# plugV13.net
KiCad netlist of a schematic drawn in EAGLE
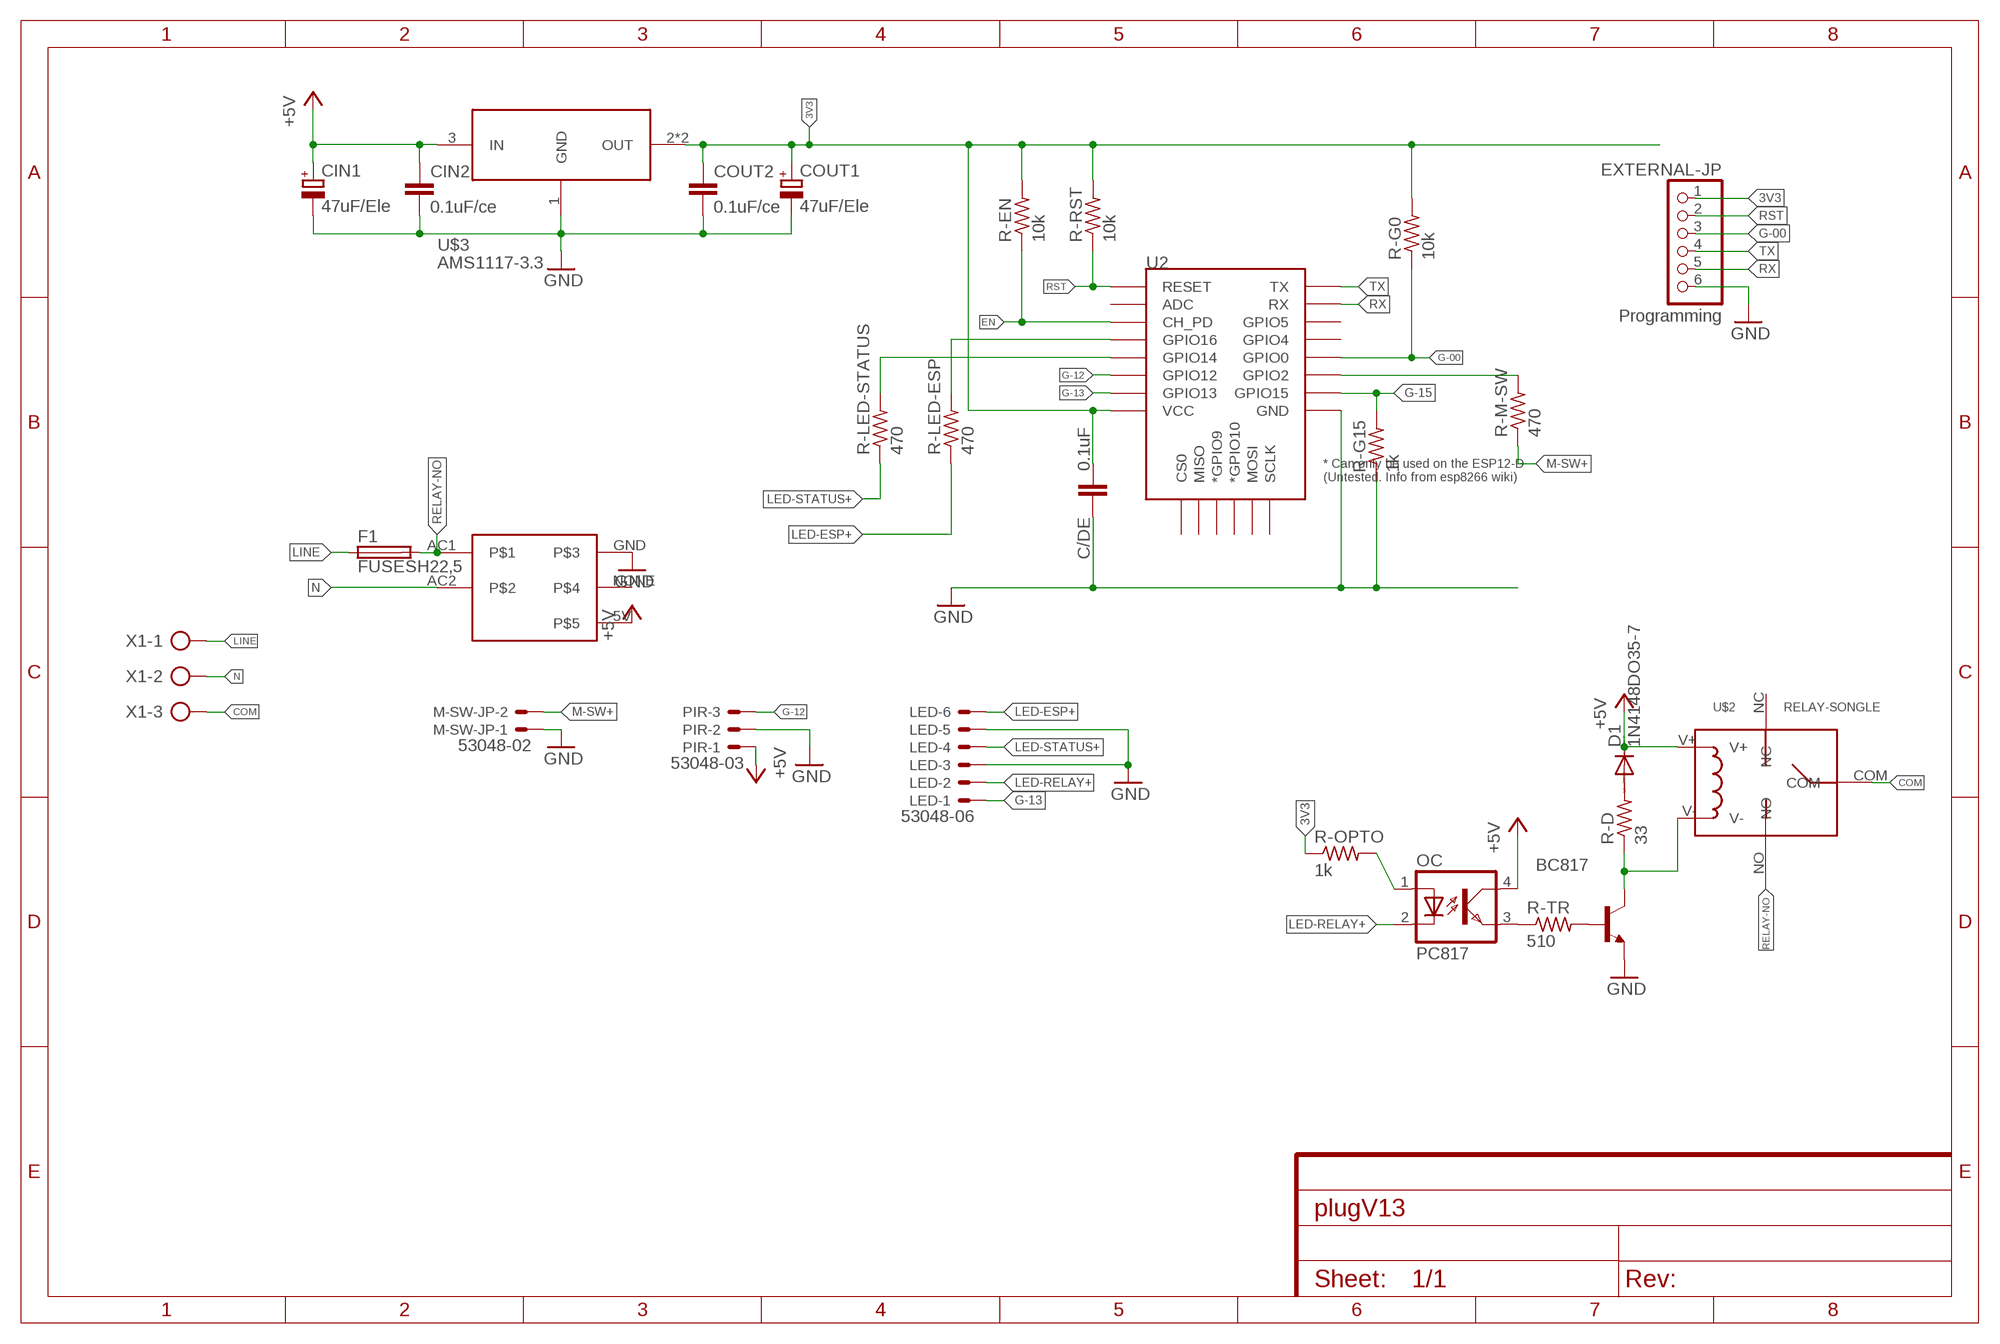
[diagram p0: schematic, sheet 1]

(export (version "E")
  (design (tool "Eeschema 10.0.6"))
  (components
    (comp (ref "BC817")
      (value "BC817-NPN-SOT23-BEC")
      (footprint "eagle-import:SOT23-BEC")
      (libsource (lib "eagle-import") (part "-NPN-SOT23-BECBC817"))
    )
    (comp (ref "C/DE")
      (value "0.1uF")
      (footprint "eagle-import:C0805")
      (libsource (lib "eagle-import") (part "C-EUC0805"))
    )
    (comp (ref "CIN1")
      (value "47uF/Ele")
      (footprint "eagle-import:E2-5")
      (libsource (lib "eagle-import") (part "CPOL-EUE2-5"))
    )
    (comp (ref "CIN2")
      (value "0.1uF/ce")
      (footprint "eagle-import:C0603K")
      (libsource (lib "eagle-import") (part "C-EUC0603K"))
    )
    (comp (ref "COUT1")
      (value "47uF/Ele")
      (footprint "eagle-import:E2-5")
      (libsource (lib "eagle-import") (part "CPOL-EUE2-5"))
    )
    (comp (ref "COUT2")
      (value "0.1uF/ce")
      (footprint "eagle-import:C0603K")
      (libsource (lib "eagle-import") (part "C-EUC0603K"))
    )
    (comp (ref "D1")
      (value "1N4148DO35-7")
      (footprint "eagle-import:DO35-7")
      (libsource (lib "eagle-import") (part "1N4148DO35-7"))
    )
    (comp (ref "EXTERNAL-JP")
      (value "Programming")
      (footprint "eagle-import:1X06")
      (libsource (lib "eagle-import") (part "PINHD-1X6"))
    )
    (comp (ref "F1")
      (value "FUSESH22,5")
      (footprint "eagle-import:SH22,5")
      (libsource (lib "eagle-import") (part "FUSESH22,5"))
    )
    (comp (ref "LED")
      (value "53048-06")
      (footprint "eagle-import:53048-06")
      (fields (field (name "MF") "WALDOM/MOLEX") (field (name "MPN") "53048-0610"))
      (libsource (lib "eagle-import") (part "53?-06048"))
    )
    (comp (ref "M-SW-JP")
      (value "53048-02")
      (footprint "eagle-import:53048-02")
      (fields (field (name "MF") "MOLEX") (field (name "MPN") "53048-0210"))
      (libsource (lib "eagle-import") (part "53?-02048"))
    )
    (comp (ref "OC")
      (value "PC817")
      (footprint "eagle-import:DIL04")
      (fields (field (name "MPN") "PC817X4J000F"))
      (libsource (lib "eagle-import") (part "PC817"))
    )
    (comp (ref "PIR")
      (value "53048-03")
      (footprint "eagle-import:53048-03")
      (fields (field (name "MF") "WALDOM/MOLEX") (field (name "MPN") "53048-0310"))
      (libsource (lib "eagle-import") (part "53?-03048"))
    )
    (comp (ref "R-D")
      (value "33")
      (footprint "eagle-import:M0805")
      (libsource (lib "eagle-import") (part "R-US_M0805"))
    )
    (comp (ref "R-EN")
      (value "10k")
      (footprint "eagle-import:R0603")
      (libsource (lib "eagle-import") (part "R-US_R0603"))
    )
    (comp (ref "R-G0")
      (value "10k")
      (footprint "eagle-import:R0603")
      (libsource (lib "eagle-import") (part "R-US_R0603"))
    )
    (comp (ref "R-G15")
      (value "1k")
      (footprint "eagle-import:R0603")
      (libsource (lib "eagle-import") (part "R-US_R0603"))
    )
    (comp (ref "R-LED-ESP")
      (value "470")
      (footprint "eagle-import:R0603")
      (libsource (lib "eagle-import") (part "R-US_R0603"))
    )
    (comp (ref "R-LED-STATUS")
      (value "470")
      (footprint "eagle-import:R0603")
      (libsource (lib "eagle-import") (part "R-US_R0603"))
    )
    (comp (ref "R-M-SW")
      (value "470")
      (footprint "eagle-import:R0603")
      (libsource (lib "eagle-import") (part "R-US_R0603"))
    )
    (comp (ref "R-OPTO")
      (value "1k")
      (footprint "eagle-import:M0805")
      (libsource (lib "eagle-import") (part "R-US_M0805"))
    )
    (comp (ref "R-RST")
      (value "10k")
      (footprint "eagle-import:R0603")
      (libsource (lib "eagle-import") (part "R-US_R0603"))
    )
    (comp (ref "R-TR")
      (value "510")
      (footprint "eagle-import:M0805")
      (libsource (lib "eagle-import") (part "R-US_M0805"))
    )
    (comp (ref "U$2")
      (value "RELAY-SONGLE")
      (footprint "eagle-import:RELAY-SONGLE")
      (libsource (lib "eagle-import") (part "RELAY-SONGLE"))
    )
    (comp (ref "U$3")
      (value "AMS1117-3.3")
      (footprint "eagle-import:SOT-223")
      (libsource (lib "eagle-import") (part "AMS1117-3.3"))
    )
    (comp (ref "U$4")
      (value "POWERSUPPLY-5V-700MA")
      (footprint "eagle-import:POWERSUPPLY-5V-700MA")
      (libsource (lib "eagle-import") (part "POWERSUPPLY-5V-700MA"))
    )
    (comp (ref "U2")
      (value "ESP12ESMD")
      (footprint "eagle-import:ESP12E-SMD")
      (libsource (lib "eagle-import") (part "ESP12ESMD"))
    )
    (comp (ref "X1")
      (value "AK300/3")
      (footprint "eagle-import:AK300_3")
      (libsource (lib "eagle-import") (part "AK300/3"))
    )
  )
  (nets
    (net (code "1") (name "+5V") (class "Default")
      (node (ref "CIN1") (pin "+") (pinfunction "+_+") (pintype "passive"))
      (node (ref "CIN2") (pin "1") (pinfunction "1_1") (pintype "passive"))
      (node (ref "D1") (pin "C") (pinfunction "C_C") (pintype "passive"))
      (node (ref "OC") (pin "4") (pinfunction "COL_4") (pintype "passive"))
      (node (ref "PIR") (pin "1") (pinfunction "S_1") (pintype "passive"))
      (node (ref "U$2") (pin "V+") (pinfunction "V+_V+") (pintype "bidirectional"))
      (node (ref "U$3") (pin "3") (pinfunction "IN_3") (pintype "input"))
      (node (ref "U$4") (pin "5V") (pinfunction "P$5_5V") (pintype "bidirectional"))
    )
    (net (code "2") (name "3V3") (class "Default")
      (node (ref "C/DE") (pin "1") (pinfunction "1_1") (pintype "passive"))
      (node (ref "COUT1") (pin "+") (pinfunction "+_+") (pintype "passive"))
      (node (ref "COUT2") (pin "1") (pinfunction "1_1") (pintype "passive"))
      (node (ref "EXTERNAL-JP") (pin "1") (pinfunction "1_1") (pintype "passive"))
      (node (ref "R-EN") (pin "2") (pinfunction "2_2") (pintype "passive"))
      (node (ref "R-G0") (pin "2") (pinfunction "2_2") (pintype "passive"))
      (node (ref "R-OPTO") (pin "1") (pinfunction "1_1") (pintype "passive"))
      (node (ref "R-RST") (pin "2") (pinfunction "2_2") (pintype "passive"))
      (node (ref "U$3") (pin "2") (pinfunction "OUT_2") (pintype "output"))
      (node (ref "U$3") (pin "4") (pinfunction "OUT_4") (pintype "output"))
      (node (ref "U2") (pin "VCC") (pinfunction "VCC_VCC") (pintype "bidirectional"))
    )
    (net (code "3") (name "COM") (class "Default")
      (node (ref "U$2") (pin "COM") (pinfunction "COM_COM") (pintype "bidirectional"))
      (node (ref "X1") (pin "3") (pinfunction "KL_3") (pintype "passive"))
    )
    (net (code "4") (name "EN") (class "Default")
      (node (ref "R-EN") (pin "1") (pinfunction "1_1") (pintype "passive"))
      (node (ref "U2") (pin "CH_PD") (pinfunction "CH_PD_CH_PD") (pintype "bidirectional"))
    )
    (net (code "5") (name "G-00") (class "Default")
      (node (ref "EXTERNAL-JP") (pin "3") (pinfunction "3_3") (pintype "passive"))
      (node (ref "R-G0") (pin "1") (pinfunction "1_1") (pintype "passive"))
      (node (ref "U2") (pin "GPIO0") (pinfunction "GPIO0_GPIO0") (pintype "bidirectional"))
    )
    (net (code "6") (name "G-12") (class "Default")
      (node (ref "PIR") (pin "3") (pinfunction "S_3") (pintype "passive"))
      (node (ref "U2") (pin "GPIO12") (pinfunction "GPIO12_GPIO12") (pintype "bidirectional"))
    )
    (net (code "7") (name "G-13") (class "Default")
      (node (ref "LED") (pin "1") (pinfunction "S_1") (pintype "passive"))
      (node (ref "U2") (pin "GPIO13") (pinfunction "GPIO13_GPIO13") (pintype "bidirectional"))
    )
    (net (code "8") (name "G-15") (class "Default")
      (node (ref "R-G15") (pin "2") (pinfunction "2_2") (pintype "passive"))
      (node (ref "U2") (pin "GPIO15") (pinfunction "GPIO15_GPIO15") (pintype "bidirectional"))
    )
    (net (code "9") (name "GND") (class "Default")
      (node (ref "BC817") (pin "E") (pinfunction "E_E") (pintype "passive"))
      (node (ref "C/DE") (pin "2") (pinfunction "2_2") (pintype "passive"))
      (node (ref "CIN1") (pin "-") (pinfunction "-_-") (pintype "passive"))
      (node (ref "CIN2") (pin "2") (pinfunction "2_2") (pintype "passive"))
      (node (ref "COUT1") (pin "-") (pinfunction "-_-") (pintype "passive"))
      (node (ref "COUT2") (pin "2") (pinfunction "2_2") (pintype "passive"))
      (node (ref "EXTERNAL-JP") (pin "6") (pinfunction "6_6") (pintype "passive"))
      (node (ref "LED") (pin "3") (pinfunction "S_3") (pintype "passive"))
      (node (ref "LED") (pin "5") (pinfunction "S_5") (pintype "passive"))
      (node (ref "M-SW-JP") (pin "1") (pinfunction "S_1") (pintype "passive"))
      (node (ref "PIR") (pin "2") (pinfunction "S_2") (pintype "passive"))
      (node (ref "R-G15") (pin "1") (pinfunction "1_1") (pintype "passive"))
      (node (ref "U$3") (pin "1") (pinfunction "GND_1") (pintype "passive"))
      (node (ref "U$4") (pin "GND") (pinfunction "P$3_GND") (pintype "bidirectional"))
      (node (ref "U2") (pin "GND") (pinfunction "GND_GND") (pintype "bidirectional"))
    )
    (net (code "10") (name "LED-ESP+") (class "Default")
      (node (ref "LED") (pin "6") (pinfunction "S_6") (pintype "passive"))
      (node (ref "R-LED-ESP") (pin "1") (pinfunction "1_1") (pintype "passive"))
    )
    (net (code "11") (name "LED-RELAY+") (class "Default")
      (node (ref "LED") (pin "2") (pinfunction "S_2") (pintype "passive"))
      (node (ref "OC") (pin "2") (pinfunction "C_2") (pintype "passive"))
    )
    (net (code "12") (name "LED-STATUS+") (class "Default")
      (node (ref "LED") (pin "4") (pinfunction "S_4") (pintype "passive"))
      (node (ref "R-LED-STATUS") (pin "1") (pinfunction "1_1") (pintype "passive"))
    )
    (net (code "13") (name "LINE") (class "Default")
      (node (ref "F1") (pin "1") (pinfunction "1_1") (pintype "passive"))
      (node (ref "X1") (pin "1") (pinfunction "KL_1") (pintype "passive"))
    )
    (net (code "14") (name "M-SW+") (class "Default")
      (node (ref "M-SW-JP") (pin "2") (pinfunction "S_2") (pintype "passive"))
      (node (ref "R-M-SW") (pin "1") (pinfunction "1_1") (pintype "passive"))
    )
    (net (code "15") (name "N") (class "Default")
      (node (ref "U$4") (pin "AC2") (pinfunction "P$2_AC2") (pintype "bidirectional"))
      (node (ref "X1") (pin "2") (pinfunction "KL_2") (pintype "passive"))
    )
    (net (code "16") (name "Net-(BC817-PadB)") (class "Default")
      (node (ref "BC817") (pin "B") (pinfunction "B_B") (pintype "passive"))
      (node (ref "R-TR") (pin "2") (pinfunction "2_2") (pintype "passive"))
    )
    (net (code "17") (name "Net-(BC817-PadC)") (class "Default")
      (node (ref "BC817") (pin "C") (pinfunction "C_C") (pintype "passive"))
      (node (ref "R-D") (pin "1") (pinfunction "1_1") (pintype "passive"))
      (node (ref "U$2") (pin "V-") (pinfunction "V-_V-") (pintype "bidirectional"))
    )
    (net (code "18") (name "Net-(D1-PadA)") (class "Default")
      (node (ref "D1") (pin "A") (pinfunction "A_A") (pintype "passive"))
      (node (ref "R-D") (pin "2") (pinfunction "2_2") (pintype "passive"))
    )
    (net (code "19") (name "Net-(OC-A)") (class "Default")
      (node (ref "OC") (pin "1") (pinfunction "A_1") (pintype "passive"))
      (node (ref "R-OPTO") (pin "2") (pinfunction "2_2") (pintype "passive"))
    )
    (net (code "20") (name "Net-(OC-EMIT)") (class "Default")
      (node (ref "OC") (pin "3") (pinfunction "EMIT_3") (pintype "passive"))
      (node (ref "R-TR") (pin "1") (pinfunction "1_1") (pintype "passive"))
    )
    (net (code "21") (name "Net-(R-LED-ESP-Pad2)") (class "Default")
      (node (ref "R-LED-ESP") (pin "2") (pinfunction "2_2") (pintype "passive"))
      (node (ref "U2") (pin "GPIO16") (pinfunction "GPIO16_GPIO16") (pintype "bidirectional"))
    )
    (net (code "22") (name "Net-(R-LED-STATUS-Pad2)") (class "Default")
      (node (ref "R-LED-STATUS") (pin "2") (pinfunction "2_2") (pintype "passive"))
      (node (ref "U2") (pin "GPIO14") (pinfunction "GPIO14_GPIO14") (pintype "bidirectional"))
    )
    (net (code "23") (name "Net-(R-M-SW-Pad2)") (class "Default")
      (node (ref "R-M-SW") (pin "2") (pinfunction "2_2") (pintype "passive"))
      (node (ref "U2") (pin "GPIO2") (pinfunction "GPIO2_GPIO2") (pintype "bidirectional"))
    )
    (net (code "24") (name "RELAY-NO") (class "Default")
      (node (ref "F1") (pin "2") (pinfunction "2_2") (pintype "passive"))
      (node (ref "U$2") (pin "NO") (pinfunction "NO_NO") (pintype "bidirectional"))
      (node (ref "U$4") (pin "AC1") (pinfunction "P$1_AC1") (pintype "bidirectional"))
    )
    (net (code "25") (name "RST") (class "Default")
      (node (ref "EXTERNAL-JP") (pin "2") (pinfunction "2_2") (pintype "passive"))
      (node (ref "R-RST") (pin "1") (pinfunction "1_1") (pintype "passive"))
      (node (ref "U2") (pin "RESET") (pinfunction "RESET_RESET") (pintype "bidirectional"))
    )
    (net (code "26") (name "RX") (class "Default")
      (node (ref "EXTERNAL-JP") (pin "5") (pinfunction "5_5") (pintype "passive"))
      (node (ref "U2") (pin "RXD0") (pinfunction "RX_RXD0") (pintype "bidirectional"))
    )
    (net (code "27") (name "TX") (class "Default")
      (node (ref "EXTERNAL-JP") (pin "4") (pinfunction "4_4") (pintype "passive"))
      (node (ref "U2") (pin "TXD0") (pinfunction "TX_TXD0") (pintype "bidirectional"))
    )
    (net (code "28") (name "unconnected-(U$2-PadNC)") (class "Default")
      (node (ref "U$2") (pin "NC") (pinfunction "NC_NC") (pintype "bidirectional"))
    )
    (net (code "29") (name "unconnected-(U$4-P$4-PadNONE)") (class "Default")
      (node (ref "U$4") (pin "NONE") (pinfunction "P$4_NONE") (pintype "bidirectional"))
    )
    (net (code "30") (name "unconnected-(U2-*GPIO9-PadGPIO9)") (class "Default")
      (node (ref "U2") (pin "GPIO9") (pinfunction "*GPIO9_GPIO9") (pintype "bidirectional"))
    )
    (net (code "31") (name "unconnected-(U2-*GPIO10-PadGPIO10)") (class "Default")
      (node (ref "U2") (pin "GPIO10") (pinfunction "*GPIO10_GPIO10") (pintype "bidirectional"))
    )
    (net (code "32") (name "unconnected-(U2-PadADC)") (class "Default")
      (node (ref "U2") (pin "ADC") (pinfunction "ADC_ADC") (pintype "bidirectional"))
    )
    (net (code "33") (name "unconnected-(U2-PadCS0)") (class "Default")
      (node (ref "U2") (pin "CS0") (pinfunction "CS0_CS0") (pintype "bidirectional"))
    )
    (net (code "34") (name "unconnected-(U2-PadGPIO4)") (class "Default")
      (node (ref "U2") (pin "GPIO4") (pinfunction "GPIO4_GPIO4") (pintype "bidirectional"))
    )
    (net (code "35") (name "unconnected-(U2-PadGPIO5)") (class "Default")
      (node (ref "U2") (pin "GPIO5") (pinfunction "GPIO5_GPIO5") (pintype "bidirectional"))
    )
    (net (code "36") (name "unconnected-(U2-PadMISO)") (class "Default")
      (node (ref "U2") (pin "MISO") (pinfunction "MISO_MISO") (pintype "bidirectional"))
    )
    (net (code "37") (name "unconnected-(U2-PadMOSI)") (class "Default")
      (node (ref "U2") (pin "MOSI") (pinfunction "MOSI_MOSI") (pintype "bidirectional"))
    )
    (net (code "38") (name "unconnected-(U2-PadSCLK)") (class "Default")
      (node (ref "U2") (pin "SCLK") (pinfunction "SCLK_SCLK") (pintype "bidirectional"))
    )
  )
)
